# SCH_555-Circuit_2025-11-27.net
KiCad netlist of a schematic drawn in EasyEDA
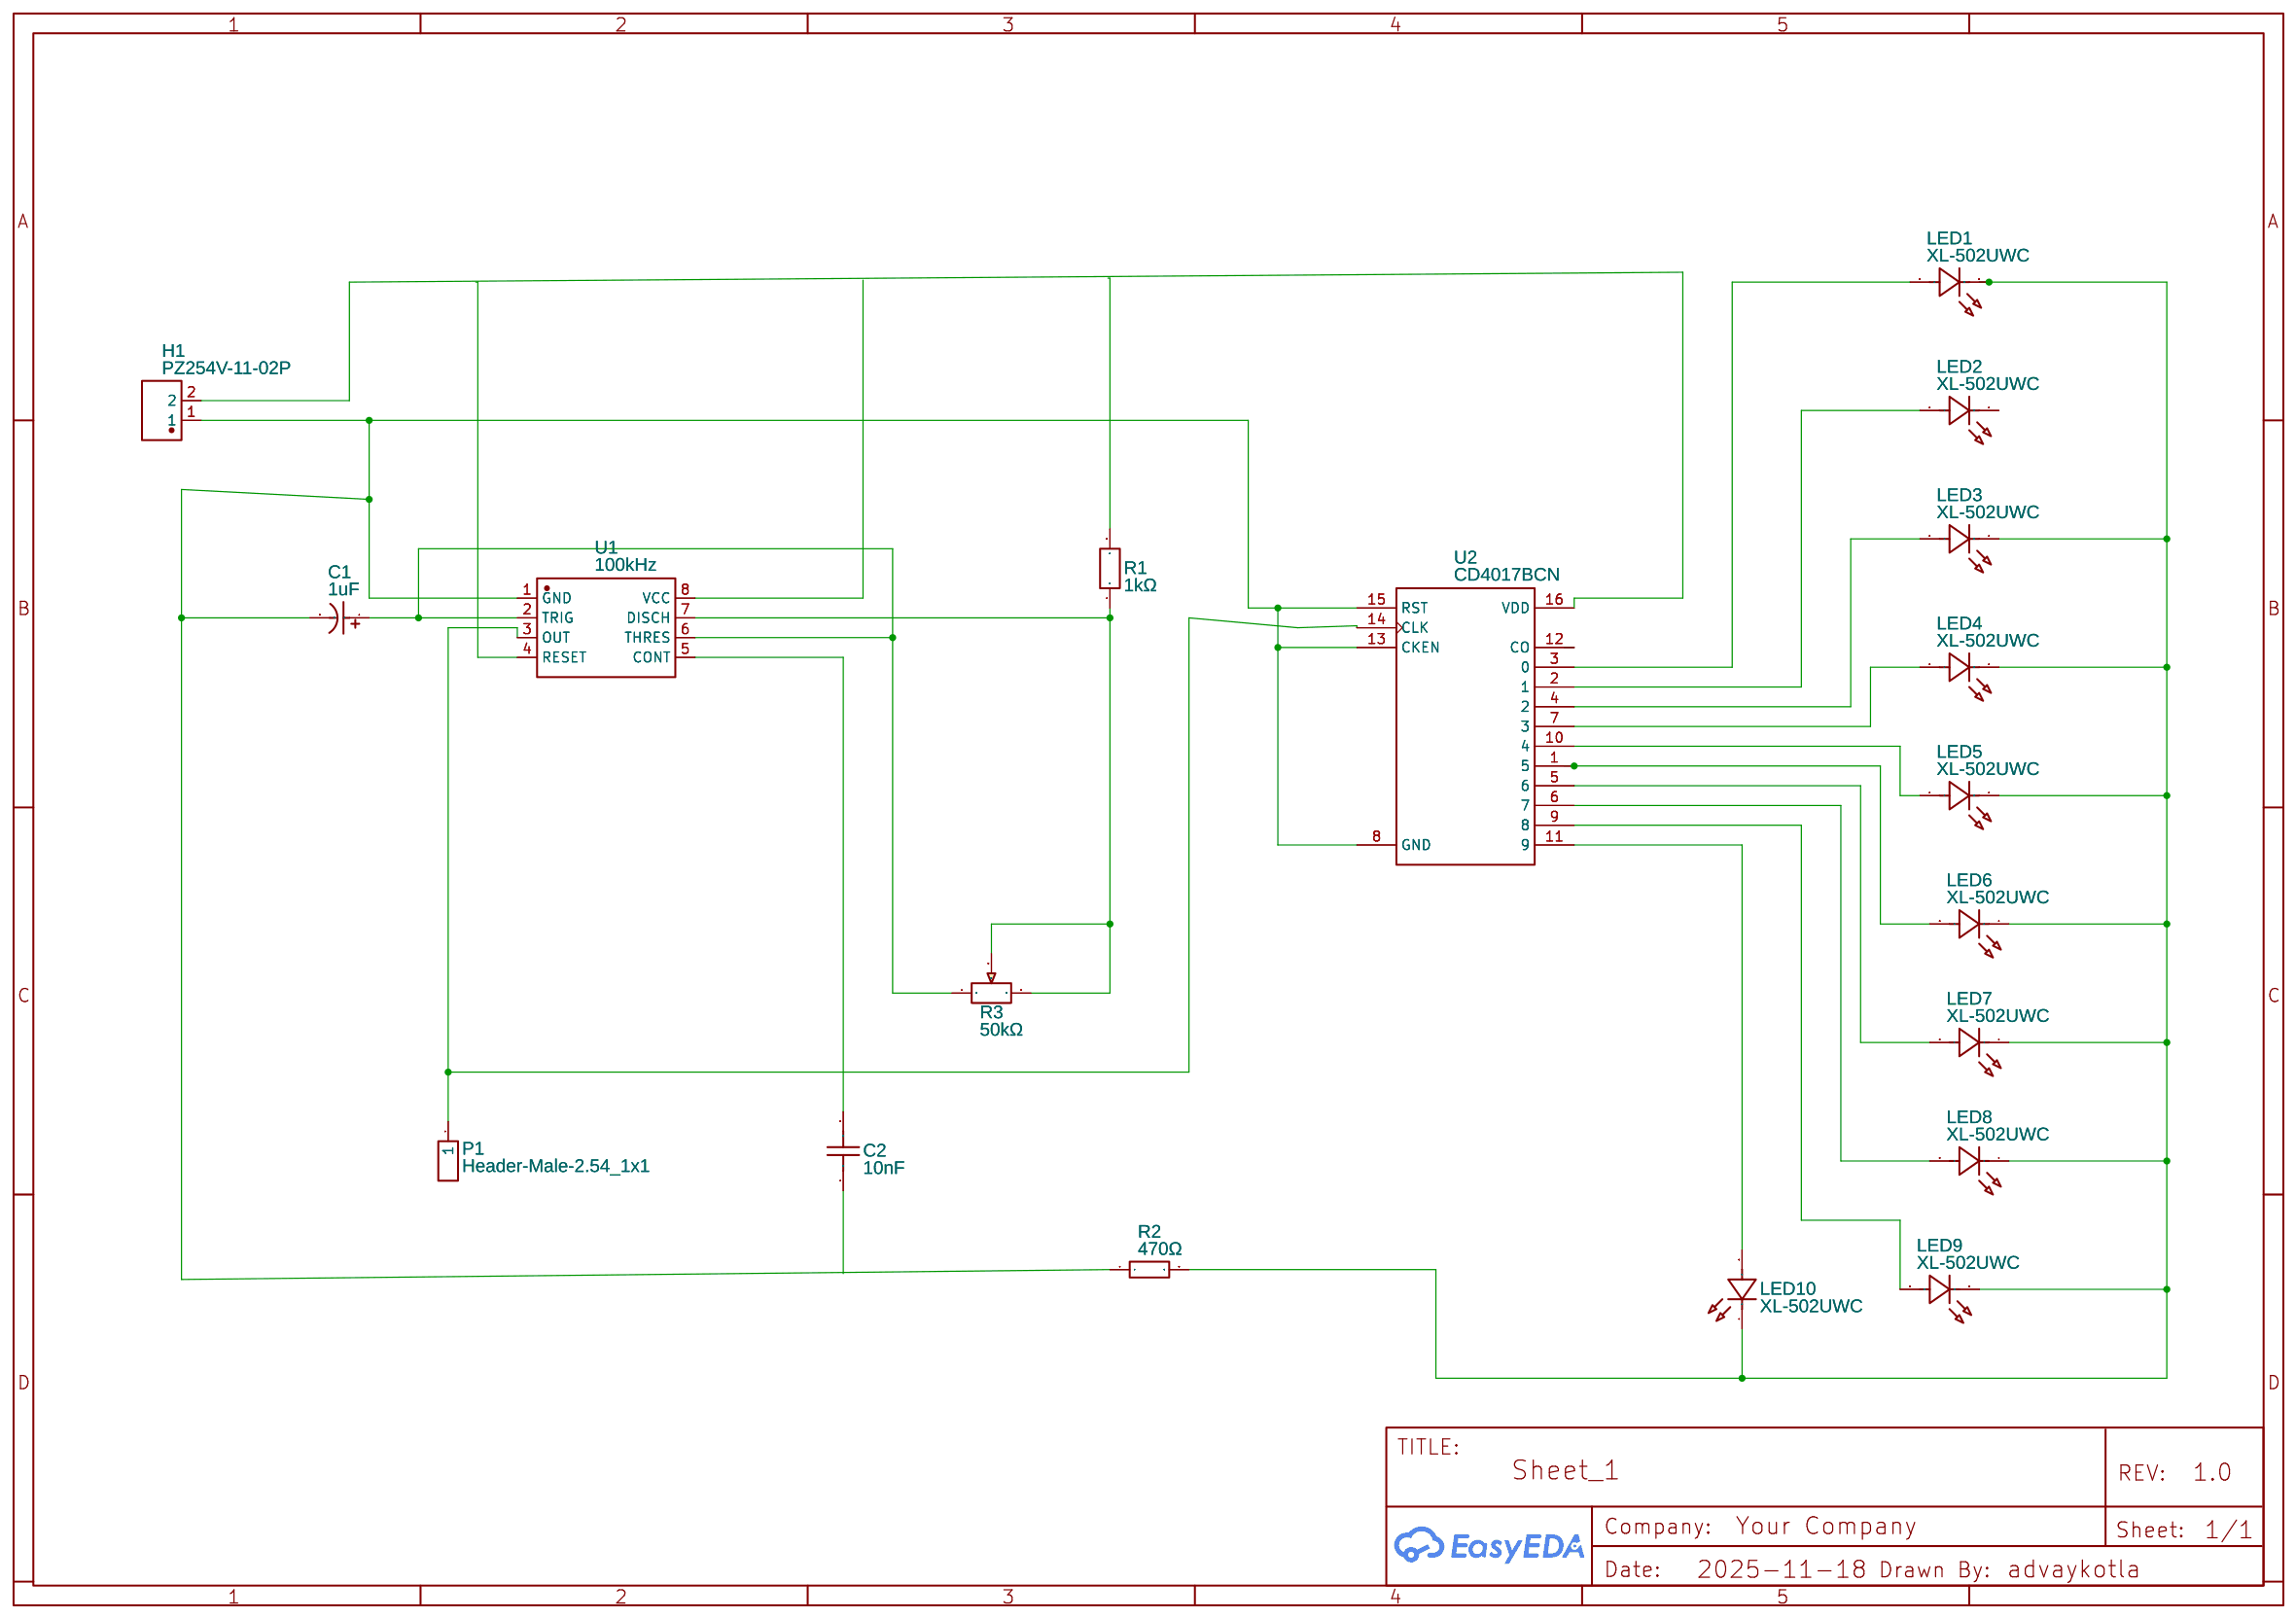
[diagram p0: schematic sheet]

(export (version "E")
  (design (tool "Eeschema 10.0.6"))
  (components
    (comp (ref "C1")
      (value "1uF")
      (fields (field (name "Manufacturer Part") "KF010M050C110A") (field (name "Manufacturer") "CapXon(丰宾)"))
      (libsource (lib "") (part "KF010M050C110A"))
    )
    (comp (ref "C2")
      (value "10nF")
      (fields (field (name "Manufacturer Part") "N09F1B103MN0B0S0N0") (field (name "Manufacturer") "STE(松田)"))
      (libsource (lib "") (part "N09F1B103MN0B0S0N0"))
    )
    (comp (ref "H1")
      (value "PZ254V-11-02P")
      (fields (field (name "Manufacturer") "XFCN(兴飞)"))
      (libsource (lib "") (part "PZ254V-11-02P"))
    )
    (comp (ref "LED1")
      (value "XL-502UWC")
      (fields (field (name "Manufacturer") "XINGLIGHT(成兴光)"))
      (libsource (lib "") (part "XL-502UWC"))
    )
    (comp (ref "LED2")
      (value "XL-502UWC")
      (fields (field (name "Manufacturer") "XINGLIGHT(成兴光)"))
      (libsource (lib "") (part "XL-502UWC"))
    )
    (comp (ref "LED3")
      (value "XL-502UWC")
      (fields (field (name "Manufacturer") "XINGLIGHT(成兴光)"))
      (libsource (lib "") (part "XL-502UWC"))
    )
    (comp (ref "LED4")
      (value "XL-502UWC")
      (fields (field (name "Manufacturer") "XINGLIGHT(成兴光)"))
      (libsource (lib "") (part "XL-502UWC"))
    )
    (comp (ref "LED5")
      (value "XL-502UWC")
      (fields (field (name "Manufacturer") "XINGLIGHT(成兴光)"))
      (libsource (lib "") (part "XL-502UWC"))
    )
    (comp (ref "LED6")
      (value "XL-502UWC")
      (fields (field (name "Manufacturer") "XINGLIGHT(成兴光)"))
      (libsource (lib "") (part "XL-502UWC"))
    )
    (comp (ref "LED7")
      (value "XL-502UWC")
      (fields (field (name "Manufacturer") "XINGLIGHT(成兴光)"))
      (libsource (lib "") (part "XL-502UWC"))
    )
    (comp (ref "LED8")
      (value "XL-502UWC")
      (fields (field (name "Manufacturer") "XINGLIGHT(成兴光)"))
      (libsource (lib "") (part "XL-502UWC"))
    )
    (comp (ref "LED9")
      (value "XL-502UWC")
      (fields (field (name "Manufacturer") "XINGLIGHT(成兴光)"))
      (libsource (lib "") (part "XL-502UWC"))
    )
    (comp (ref "LED10")
      (value "XL-502UWC")
      (fields (field (name "Manufacturer") "XINGLIGHT(成兴光)"))
      (libsource (lib "") (part "XL-502UWC_1"))
    )
    (comp (ref "P1")
      (value "Header-Male-2.54_1x1")
      (fields (field (name "Manufacturer Part") "2.54-1*1P针") (field (name "Manufacturer") "BOOMELE(博穆精密)"))
      (libsource (lib "") (part "Header-Male-2.54_1x1"))
    )
    (comp (ref "R1")
      (value "1kΩ")
      (fields (field (name "Manufacturer Part") "MF1/4W-1KΩ±1%T52") (field (name "Manufacturer") "华星机电"))
      (libsource (lib "") (part "MF1/4W-1KΩ±1%T52"))
    )
    (comp (ref "R2")
      (value "470Ω")
      (fields
        (field (name "Manufacturer Part") "MFR0W4F4700A50")
        (field (name "Manufacturer") "UNI-ROYAL(厚声)")
      )
      (libsource (lib "") (part "MFR0W4F4700A50"))
    )
    (comp (ref "R3")
      (value "50kΩ")
      (fields (field (name "Manufacturer Part") "3296X-1-503") (field (name "Manufacturer") "BOCHEN(博晨)"))
      (libsource (lib "") (part "3296X-1-503_C118912"))
    )
    (comp (ref "U1")
      (value "100kHz")
      (fields (field (name "Manufacturer Part") "NE555P") (field (name "Manufacturer") "TI(德州仪器)"))
      (libsource (lib "") (part "NE555P"))
    )
    (comp (ref "U2") (value "CD4017BCN") (libsource (lib "") (part "CD4017BCN")))
  )
  (nets
    (net (code "1") (name "Net-(LED1-A)") (class "Default")
      (node (ref "LED1") (pin "2") (pinfunction "A_2") (pintype "unspecified"))
      (node (ref "U2") (pin "3") (pinfunction "0_3") (pintype "output"))
    )
    (net (code "2") (name "Net-(LED1-K)") (class "Default")
      (node (ref "LED1") (pin "1") (pinfunction "K_1") (pintype "unspecified"))
      (node (ref "LED10") (pin "1") (pinfunction "K_1") (pintype "unspecified"))
      (node (ref "LED3") (pin "1") (pinfunction "K_1") (pintype "unspecified"))
      (node (ref "LED4") (pin "1") (pinfunction "K_1") (pintype "unspecified"))
      (node (ref "LED5") (pin "1") (pinfunction "K_1") (pintype "unspecified"))
      (node (ref "LED6") (pin "1") (pinfunction "K_1") (pintype "unspecified"))
      (node (ref "LED7") (pin "1") (pinfunction "K_1") (pintype "unspecified"))
      (node (ref "LED8") (pin "1") (pinfunction "K_1") (pintype "unspecified"))
      (node (ref "LED9") (pin "1") (pinfunction "K_1") (pintype "unspecified"))
      (node (ref "R2") (pin "2") (pinfunction "2_2") (pintype "input"))
    )
    (net (code "3") (name "Net-(LED2-A)") (class "Default")
      (node (ref "LED2") (pin "2") (pinfunction "A_2") (pintype "unspecified"))
      (node (ref "U2") (pin "2") (pinfunction "1_2") (pintype "output"))
    )
    (net (code "4") (name "Net-(LED3-A)") (class "Default")
      (node (ref "LED3") (pin "2") (pinfunction "A_2") (pintype "unspecified"))
      (node (ref "U2") (pin "4") (pinfunction "2_4") (pintype "output"))
    )
    (net (code "5") (name "Net-(LED4-A)") (class "Default")
      (node (ref "LED4") (pin "2") (pinfunction "A_2") (pintype "unspecified"))
      (node (ref "U2") (pin "7") (pinfunction "3_7") (pintype "output"))
    )
    (net (code "6") (name "Net-(LED5-A)") (class "Default")
      (node (ref "LED5") (pin "2") (pinfunction "A_2") (pintype "unspecified"))
      (node (ref "U2") (pin "10") (pinfunction "4_10") (pintype "output"))
    )
    (net (code "7") (name "Net-(LED6-A)") (class "Default")
      (node (ref "LED6") (pin "2") (pinfunction "A_2") (pintype "unspecified"))
      (node (ref "U2") (pin "1") (pinfunction "5_1") (pintype "output"))
    )
    (net (code "8") (name "Net-(LED7-A)") (class "Default")
      (node (ref "LED7") (pin "2") (pinfunction "A_2") (pintype "unspecified"))
      (node (ref "U2") (pin "5") (pinfunction "6_5") (pintype "output"))
    )
    (net (code "9") (name "Net-(LED8-A)") (class "Default")
      (node (ref "LED8") (pin "2") (pinfunction "A_2") (pintype "unspecified"))
      (node (ref "U2") (pin "6") (pinfunction "7_6") (pintype "output"))
    )
    (net (code "10") (name "Net-(LED9-A)") (class "Default")
      (node (ref "LED9") (pin "2") (pinfunction "A_2") (pintype "unspecified"))
      (node (ref "U2") (pin "9") (pinfunction "8_9") (pintype "output"))
    )
    (net (code "11") (name "Net-(LED10-A)") (class "Default")
      (node (ref "LED10") (pin "2") (pinfunction "A_2") (pintype "unspecified"))
      (node (ref "U2") (pin "11") (pinfunction "9_11") (pintype "output"))
    )
    (net (code "12") (name "Net-(U1-CONT)") (class "Default")
      (node (ref "C2") (pin "2") (pinfunction "2_2") (pintype "unspecified"))
      (node (ref "U1") (pin "5") (pinfunction "CONT_5") (pintype "unspecified"))
    )
    (net (code "13") (name "Net-(U1-DISCH)") (class "Default")
      (node (ref "R1") (pin "1") (pinfunction "1_1") (pintype "unspecified"))
      (node (ref "R3") (pin "2") (pinfunction "2_2") (pintype "input"))
      (node (ref "R3") (pin "3") (pinfunction "3_3") (pintype "input"))
      (node (ref "U1") (pin "7") (pinfunction "DISCH_7") (pintype "unspecified"))
    )
    (net (code "14") (name "Net-(U1-GND)") (class "Default")
      (node (ref "C1") (pin "2") (pinfunction "2_2") (pintype "input"))
      (node (ref "H1") (pin "1") (pinfunction "1_1") (pintype "unspecified"))
      (node (ref "R2") (pin "1") (pinfunction "1_1") (pintype "input"))
      (node (ref "U1") (pin "1") (pinfunction "GND_1") (pintype "unspecified"))
      (node (ref "U2") (pin "13") (pinfunction "CKEN_13") (pintype "unspecified"))
      (node (ref "U2") (pin "15") (pinfunction "RST_15") (pintype "unspecified"))
      (node (ref "U2") (pin "8") (pinfunction "GND_8") (pintype "passive"))
    )
    (net (code "15") (name "Net-(U1-OUT)") (class "Default")
      (node (ref "P1") (pin "1") (pinfunction "1_1") (pintype "input"))
      (node (ref "U1") (pin "3") (pinfunction "OUT_3") (pintype "unspecified"))
      (node (ref "U2") (pin "14") (pinfunction "CLK_14") (pintype "unspecified"))
    )
    (net (code "16") (name "Net-(U1-THRES)") (class "Default")
      (node (ref "C1") (pin "1") (pinfunction "1_1") (pintype "input"))
      (node (ref "R3") (pin "1") (pinfunction "1_1") (pintype "input"))
      (node (ref "U1") (pin "2") (pinfunction "TRIG_2") (pintype "unspecified"))
      (node (ref "U1") (pin "6") (pinfunction "THRES_6") (pintype "unspecified"))
    )
    (net (code "17") (name "Net-(U2-VDD)") (class "Default")
      (node (ref "H1") (pin "2") (pinfunction "2_2") (pintype "unspecified"))
      (node (ref "U2") (pin "16") (pinfunction "VDD_16") (pintype "passive"))
    )
    (net (code "18") (name "unconnected-(C2-Pad1)") (class "Default")
      (node (ref "C2") (pin "1") (pinfunction "1_1") (pintype "unspecified"))
    )
    (net (code "19") (name "unconnected-(LED2-K-Pad1)") (class "Default")
      (node (ref "LED2") (pin "1") (pinfunction "K_1") (pintype "unspecified"))
    )
    (net (code "20") (name "unconnected-(R1-Pad2)") (class "Default")
      (node (ref "R1") (pin "2") (pinfunction "2_2") (pintype "unspecified"))
    )
    (net (code "21") (name "unconnected-(U1-RESET-Pad4)") (class "Default")
      (node (ref "U1") (pin "4") (pinfunction "RESET_4") (pintype "unspecified"))
    )
    (net (code "22") (name "unconnected-(U1-VCC-Pad8)") (class "Default")
      (node (ref "U1") (pin "8") (pinfunction "VCC_8") (pintype "unspecified"))
    )
    (net (code "23") (name "unconnected-(U2-CO-Pad12)") (class "Default")
      (node (ref "U2") (pin "12") (pinfunction "CO_12") (pintype "output"))
    )
  )
)
